# mLRS-rx-tx-E77-E22-dual-easysolder-v011.net
KiCad netlist of a schematic drawn in EAGLE
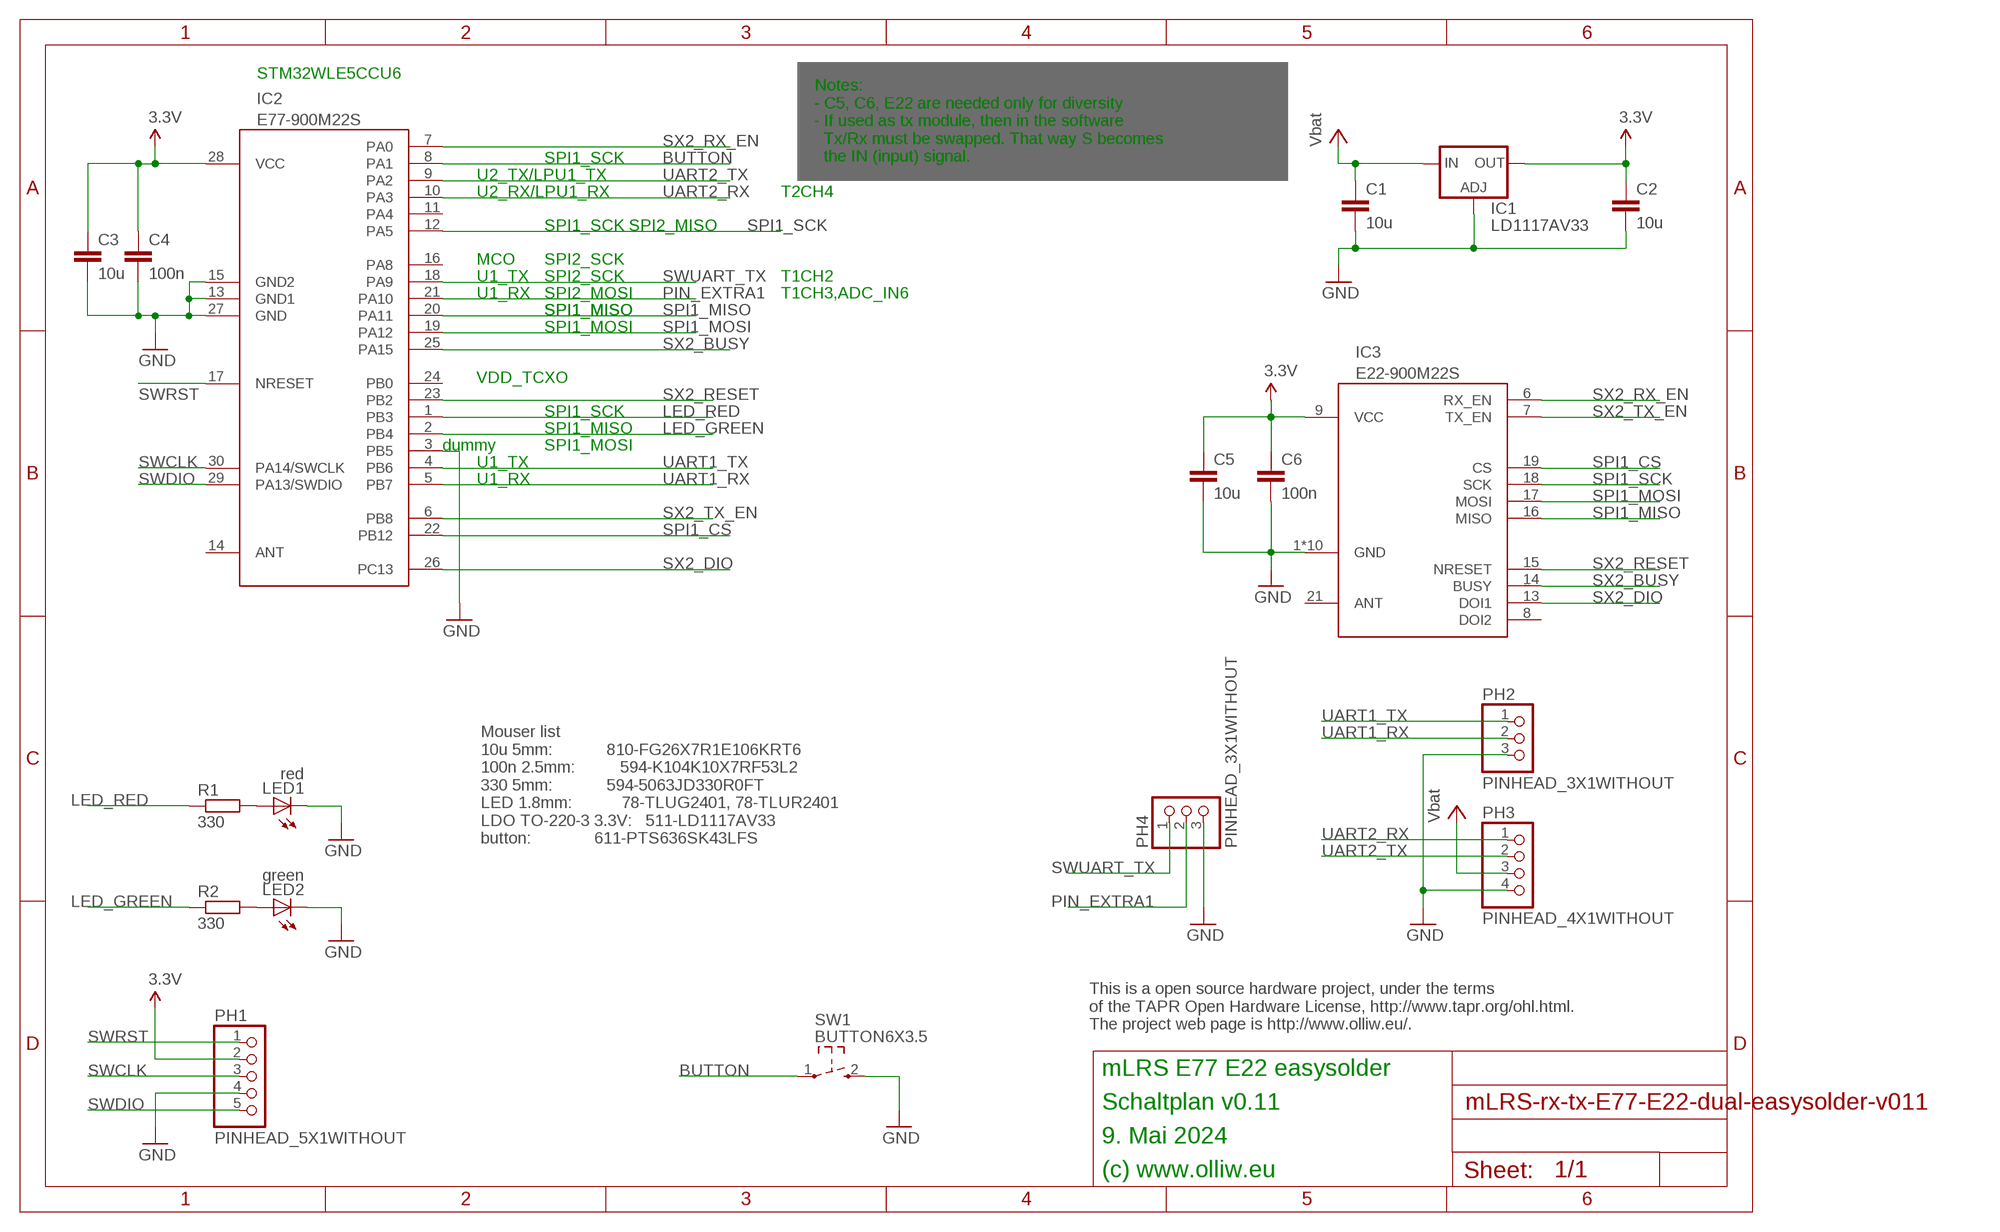
[diagram p0: schematic, sheet 1]

(export (version "E")
  (design (tool "Eeschema 10.0.6"))
  (components
    (comp (ref "C1")
      (value "10u")
      (footprint "eagle-import:C050-045X075")
      (libsource (lib "eagle-import") (part "C-EU050-045X075"))
    )
    (comp (ref "C2")
      (value "10u")
      (footprint "eagle-import:C050-045X075")
      (libsource (lib "eagle-import") (part "C-EU050-045X075"))
    )
    (comp (ref "C3")
      (value "10u")
      (footprint "eagle-import:C050-024X044")
      (libsource (lib "eagle-import") (part "C-EU050-024X044"))
    )
    (comp (ref "C4")
      (value "100n")
      (footprint "eagle-import:C025-024X044")
      (libsource (lib "eagle-import") (part "C-EU025-024X044"))
    )
    (comp (ref "C5")
      (value "10u")
      (footprint "eagle-import:C050-024X044")
      (libsource (lib "eagle-import") (part "C-EU050-024X044"))
    )
    (comp (ref "C6")
      (value "100n")
      (footprint "eagle-import:C025-024X044")
      (libsource (lib "eagle-import") (part "C-EU025-024X044"))
    )
    (comp (ref "IC1")
      (value "LD1117AV33")
      (footprint "eagle-import:TO220L1")
      (libsource (lib "eagle-import") (part "LD117A?V33"))
    )
    (comp (ref "IC2")
      (value "E77-900M22S")
      (footprint "eagle-import:E77-900M22S")
      (libsource (lib "eagle-import") (part "E77-900M22S"))
    )
    (comp (ref "IC3")
      (value "E22-900M22S")
      (footprint "eagle-import:E22-900M22S")
      (libsource (lib "eagle-import") (part "E22-900M22S"))
    )
    (comp (ref "LED1")
      (value "red")
      (footprint "eagle-import:LED1.8MM")
      (libsource (lib "eagle-import") (part "LED1.8MM"))
    )
    (comp (ref "LED2")
      (value "green")
      (footprint "eagle-import:LED1.8MM")
      (libsource (lib "eagle-import") (part "LED1.8MM"))
    )
    (comp (ref "PH1")
      (value "PINHEAD_5X1WITHOUT")
      (footprint "eagle-import:PINHEAD_5X1_WO")
      (libsource (lib "eagle-import") (part "PINHEAD_5X1WITHOUT"))
    )
    (comp (ref "PH2")
      (value "PINHEAD_3X1WITHOUT")
      (footprint "eagle-import:PINHEAD_3X1_WO")
      (libsource (lib "eagle-import") (part "PINHEAD_3X1WITHOUT"))
    )
    (comp (ref "PH3")
      (value "PINHEAD_4X1WITHOUT")
      (footprint "eagle-import:PINHEAD_4X1_WO")
      (libsource (lib "eagle-import") (part "PINHEAD_4X1WITHOUT"))
    )
    (comp (ref "PH4")
      (value "PINHEAD_3X1WITHOUT")
      (footprint "eagle-import:PINHEAD_3X1_WO")
      (libsource (lib "eagle-import") (part "PINHEAD_3X1WITHOUT"))
    )
    (comp (ref "R1")
      (value "330")
      (footprint "eagle-import:R0204_6.25")
      (libsource (lib "eagle-import") (part "R_EUR0204/6.25"))
    )
    (comp (ref "R2")
      (value "330")
      (footprint "eagle-import:R0204_6.25")
      (libsource (lib "eagle-import") (part "R_EUR0204/6.25"))
    )
    (comp (ref "SW1")
      (value "BUTTON6X3.5")
      (footprint "eagle-import:BUTTON-THT")
      (libsource (lib "eagle-import") (part "BUTTON6X3.5"))
    )
  )
  (nets
    (net (code "1") (name "/BUTTON") (class "Default")
      (node (ref "IC2") (pin "8") (pinfunction "PA1_8") (pintype "bidirectional"))
      (node (ref "SW1") (pin "1") (pinfunction "1_1") (pintype "passive"))
    )
    (net (code "2") (name "/LED_GREEN") (class "Default")
      (node (ref "IC2") (pin "2") (pinfunction "PB4_2") (pintype "bidirectional"))
      (node (ref "R2") (pin "1") (pinfunction "1_1") (pintype "passive"))
    )
    (net (code "3") (name "/LED_RED") (class "Default")
      (node (ref "IC2") (pin "1") (pinfunction "PB3_1") (pintype "bidirectional"))
      (node (ref "R1") (pin "1") (pinfunction "1_1") (pintype "passive"))
    )
    (net (code "4") (name "/PIN_EXTRA1") (class "Default")
      (node (ref "IC2") (pin "21") (pinfunction "PA10_21") (pintype "bidirectional"))
      (node (ref "PH4") (pin "2") (pinfunction "3_2") (pintype "passive"))
    )
    (net (code "5") (name "/SPI1_CS") (class "Default")
      (node (ref "IC2") (pin "22") (pinfunction "PB12_22") (pintype "bidirectional"))
      (node (ref "IC3") (pin "19") (pinfunction "CS_19") (pintype "bidirectional"))
    )
    (net (code "6") (name "/SPI1_MISO") (class "Default")
      (node (ref "IC2") (pin "20") (pinfunction "PA11_20") (pintype "bidirectional"))
      (node (ref "IC3") (pin "16") (pinfunction "MISO_16") (pintype "bidirectional"))
    )
    (net (code "7") (name "/SPI1_MOSI") (class "Default")
      (node (ref "IC2") (pin "19") (pinfunction "PA12_19") (pintype "bidirectional"))
      (node (ref "IC3") (pin "17") (pinfunction "MOSI_17") (pintype "bidirectional"))
    )
    (net (code "8") (name "/SPI1_SCK") (class "Default")
      (node (ref "IC2") (pin "12") (pinfunction "PA5_12") (pintype "bidirectional"))
      (node (ref "IC3") (pin "18") (pinfunction "SCK_18") (pintype "bidirectional"))
    )
    (net (code "9") (name "/SWCLK") (class "Default")
      (node (ref "IC2") (pin "30") (pinfunction "PA14/SWCLK_30") (pintype "bidirectional"))
      (node (ref "PH1") (pin "3") (pinfunction "3_3") (pintype "passive"))
    )
    (net (code "10") (name "/SWDIO") (class "Default")
      (node (ref "IC2") (pin "29") (pinfunction "PA13/SWDIO_29") (pintype "bidirectional"))
      (node (ref "PH1") (pin "5") (pinfunction "5_5") (pintype "passive"))
    )
    (net (code "11") (name "/SWRST") (class "Default")
      (node (ref "IC2") (pin "17") (pinfunction "NRESET_17") (pintype "input"))
      (node (ref "PH1") (pin "1") (pinfunction "1_1") (pintype "passive"))
    )
    (net (code "12") (name "/SWUART_TX") (class "Default")
      (node (ref "IC2") (pin "18") (pinfunction "PA9_18") (pintype "bidirectional"))
      (node (ref "PH4") (pin "1") (pinfunction "1_1") (pintype "passive"))
    )
    (net (code "13") (name "/SX2_BUSY") (class "Default")
      (node (ref "IC2") (pin "25") (pinfunction "PA15_25") (pintype "bidirectional"))
      (node (ref "IC3") (pin "14") (pinfunction "BUSY_14") (pintype "bidirectional"))
    )
    (net (code "14") (name "/SX2_DIO") (class "Default")
      (node (ref "IC2") (pin "26") (pinfunction "PC13_26") (pintype "bidirectional"))
      (node (ref "IC3") (pin "13") (pinfunction "DOI1_13") (pintype "bidirectional"))
    )
    (net (code "15") (name "/SX2_RESET") (class "Default")
      (node (ref "IC2") (pin "23") (pinfunction "PB2_23") (pintype "bidirectional"))
      (node (ref "IC3") (pin "15") (pinfunction "NRESET_15") (pintype "input"))
    )
    (net (code "16") (name "/SX2_RX_EN") (class "Default")
      (node (ref "IC2") (pin "7") (pinfunction "PA0_7") (pintype "bidirectional"))
      (node (ref "IC3") (pin "6") (pinfunction "RX_EN_6") (pintype "bidirectional"))
    )
    (net (code "17") (name "/SX2_TX_EN") (class "Default")
      (node (ref "IC2") (pin "6") (pinfunction "PB8_6") (pintype "bidirectional"))
      (node (ref "IC3") (pin "7") (pinfunction "TX_EN_7") (pintype "bidirectional"))
    )
    (net (code "18") (name "/UART1_RX") (class "Default")
      (node (ref "IC2") (pin "5") (pinfunction "PB7_5") (pintype "bidirectional"))
      (node (ref "PH2") (pin "2") (pinfunction "3_2") (pintype "passive"))
    )
    (net (code "19") (name "/UART1_TX") (class "Default")
      (node (ref "IC2") (pin "4") (pinfunction "PB6_4") (pintype "bidirectional"))
      (node (ref "PH2") (pin "1") (pinfunction "1_1") (pintype "passive"))
    )
    (net (code "20") (name "/UART2_RX") (class "Default")
      (node (ref "IC2") (pin "10") (pinfunction "PA3_10") (pintype "bidirectional"))
      (node (ref "PH3") (pin "1") (pinfunction "1_1") (pintype "passive"))
    )
    (net (code "21") (name "/UART2_TX") (class "Default")
      (node (ref "IC2") (pin "9") (pinfunction "PA2_9") (pintype "bidirectional"))
      (node (ref "PH3") (pin "2") (pinfunction "2_2") (pintype "passive"))
    )
    (net (code "22") (name "3.3V") (class "Default")
      (node (ref "C2") (pin "1") (pinfunction "1_1") (pintype "passive"))
      (node (ref "C3") (pin "1") (pinfunction "1_1") (pintype "passive"))
      (node (ref "C4") (pin "1") (pinfunction "1_1") (pintype "passive"))
      (node (ref "C5") (pin "1") (pinfunction "1_1") (pintype "passive"))
      (node (ref "C6") (pin "1") (pinfunction "1_1") (pintype "passive"))
      (node (ref "IC1") (pin "2") (pinfunction "OUT_2") (pintype "passive"))
      (node (ref "IC2") (pin "28") (pinfunction "VCC_28") (pintype "power_in"))
      (node (ref "IC3") (pin "9") (pinfunction "VCC_9") (pintype "power_in"))
      (node (ref "PH1") (pin "2") (pinfunction "2_2") (pintype "passive"))
    )
    (net (code "23") (name "GND") (class "Default")
      (node (ref "C1") (pin "2") (pinfunction "2_2") (pintype "passive"))
      (node (ref "C2") (pin "2") (pinfunction "2_2") (pintype "passive"))
      (node (ref "C3") (pin "2") (pinfunction "2_2") (pintype "passive"))
      (node (ref "C4") (pin "2") (pinfunction "2_2") (pintype "passive"))
      (node (ref "C5") (pin "2") (pinfunction "2_2") (pintype "passive"))
      (node (ref "C6") (pin "2") (pinfunction "2_2") (pintype "passive"))
      (node (ref "IC1") (pin "1") (pinfunction "ADJ_1") (pintype "input"))
      (node (ref "IC2") (pin "13") (pinfunction "GND1_13") (pintype "power_in"))
      (node (ref "IC2") (pin "15") (pinfunction "GND2_15") (pintype "power_in"))
      (node (ref "IC2") (pin "27") (pinfunction "GND_27") (pintype "power_in"))
      (node (ref "IC2") (pin "3") (pinfunction "PB5_3") (pintype "bidirectional"))
      (node (ref "IC3") (pin "1") (pinfunction "GND_1") (pintype "power_in"))
      (node (ref "IC3") (pin "10") (pinfunction "GND_10") (pintype "power_in"))
      (node (ref "IC3") (pin "11") (pinfunction "GND_11") (pintype "power_in"))
      (node (ref "IC3") (pin "12") (pinfunction "GND_12") (pintype "power_in"))
      (node (ref "IC3") (pin "2") (pinfunction "GND_2") (pintype "power_in"))
      (node (ref "IC3") (pin "20") (pinfunction "GND_20") (pintype "power_in"))
      (node (ref "IC3") (pin "22") (pinfunction "GND_22") (pintype "power_in"))
      (node (ref "IC3") (pin "3") (pinfunction "GND_3") (pintype "power_in"))
      (node (ref "IC3") (pin "4") (pinfunction "GND_4") (pintype "power_in"))
      (node (ref "IC3") (pin "5") (pinfunction "GND_5") (pintype "power_in"))
      (node (ref "LED1") (pin "K") (pinfunction "C_K") (pintype "passive"))
      (node (ref "LED2") (pin "K") (pinfunction "C_K") (pintype "passive"))
      (node (ref "PH1") (pin "4") (pinfunction "4_4") (pintype "passive"))
      (node (ref "PH2") (pin "3") (pinfunction "5_3") (pintype "passive"))
      (node (ref "PH3") (pin "4") (pinfunction "4_4") (pintype "passive"))
      (node (ref "PH4") (pin "3") (pinfunction "5_3") (pintype "passive"))
      (node (ref "SW1") (pin "2") (pinfunction "3_2") (pintype "passive"))
    )
    (net (code "24") (name "Net-(LED1-PadA)") (class "Default")
      (node (ref "LED1") (pin "A") (pinfunction "A_A") (pintype "passive"))
      (node (ref "R1") (pin "2") (pinfunction "2_2") (pintype "passive"))
    )
    (net (code "25") (name "Net-(LED2-PadA)") (class "Default")
      (node (ref "LED2") (pin "A") (pinfunction "A_A") (pintype "passive"))
      (node (ref "R2") (pin "2") (pinfunction "2_2") (pintype "passive"))
    )
    (net (code "26") (name "Vbat") (class "Default")
      (node (ref "C1") (pin "1") (pinfunction "1_1") (pintype "passive"))
      (node (ref "IC1") (pin "3") (pinfunction "IN_3") (pintype "input"))
      (node (ref "PH3") (pin "3") (pinfunction "3_3") (pintype "passive"))
    )
    (net (code "27") (name "unconnected-(IC2-ANT-Pad14)") (class "Default")
      (node (ref "IC2") (pin "14") (pinfunction "ANT_14") (pintype "bidirectional"))
    )
    (net (code "28") (name "unconnected-(IC2-PA4-Pad11)") (class "Default")
      (node (ref "IC2") (pin "11") (pinfunction "PA4_11") (pintype "bidirectional"))
    )
    (net (code "29") (name "unconnected-(IC2-PA8-Pad16)") (class "Default")
      (node (ref "IC2") (pin "16") (pinfunction "PA8_16") (pintype "bidirectional"))
    )
    (net (code "30") (name "unconnected-(IC2-PB0-Pad24)") (class "Default")
      (node (ref "IC2") (pin "24") (pinfunction "PB0_24") (pintype "bidirectional"))
    )
    (net (code "31") (name "unconnected-(IC3-ANT-Pad21)") (class "Default")
      (node (ref "IC3") (pin "21") (pinfunction "ANT_21") (pintype "bidirectional"))
    )
    (net (code "32") (name "unconnected-(IC3-DOI2-Pad8)") (class "Default")
      (node (ref "IC3") (pin "8") (pinfunction "DOI2_8") (pintype "bidirectional"))
    )
  )
)
